# Multivibrator.net
KiCad netlist of a schematic drawn in Altium Designer
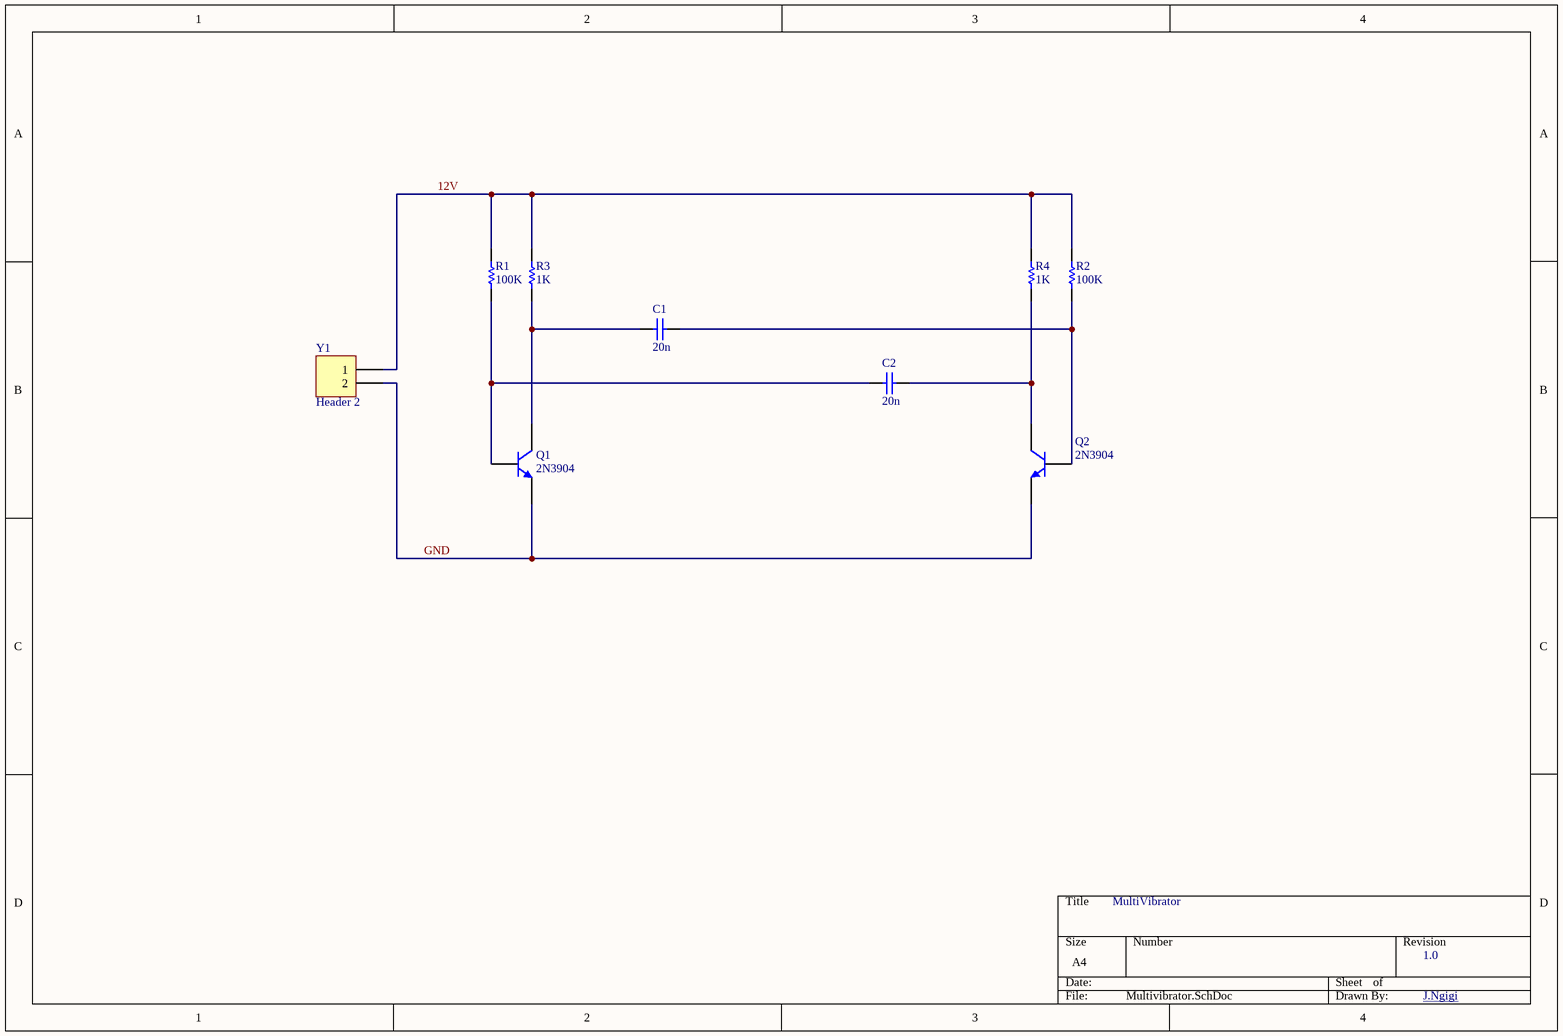
[diagram p0: Multivibrator.SchDoc]

(export (version "E")
  (design (tool "Eeschema 10.0.6"))
  (components
    (comp (ref "C1")
      (value "20n")
      (footprint "RAD-0.3")
      (description "Capacitor")
      (fields (field (name "PUBLISHER") "Altium Limited"))
      (libsource (lib "Miscellaneous Devices") (part "Cap"))
    )
    (comp (ref "C2")
      (value "20n")
      (footprint "RAD-0.3")
      (description "Capacitor")
      (fields (field (name "PUBLISHER") "Altium Limited"))
      (libsource (lib "Miscellaneous Devices") (part "Cap"))
    )
    (comp (ref "Q1")
      (value "2N3904")
      (footprint "TO-92A")
      (description "NPN General Purpose Amplifier")
      (fields (field (name "PUBLISHER") "Altium Limited"))
      (libsource (lib "Miscellaneous Devices") (part "2N3904"))
    )
    (comp (ref "Q2")
      (value "2N3904")
      (footprint "TO-92A")
      (description "NPN General Purpose Amplifier")
      (fields (field (name "PUBLISHER") "Altium Limited"))
      (libsource (lib "Miscellaneous Devices") (part "2N3904"))
    )
    (comp (ref "R1")
      (value "100K")
      (footprint "AXIAL-0.3")
      (description "Resistor")
      (fields (field (name "PUBLISHER") "Altium Limited"))
      (libsource (lib "Miscellaneous Devices") (part "Res1"))
    )
    (comp (ref "R2")
      (value "100K")
      (footprint "AXIAL-0.3")
      (description "Resistor")
      (fields (field (name "PUBLISHER") "Altium Limited"))
      (libsource (lib "Miscellaneous Devices") (part "Res1"))
    )
    (comp (ref "R3")
      (value "1K")
      (footprint "AXIAL-0.3")
      (description "Resistor")
      (fields (field (name "PUBLISHER") "Altium Limited"))
      (libsource (lib "Miscellaneous Devices") (part "Res1"))
    )
    (comp (ref "R4")
      (value "1K")
      (footprint "AXIAL-0.3")
      (description "Resistor")
      (fields (field (name "PUBLISHER") "Altium Limited"))
      (libsource (lib "Miscellaneous Devices") (part "Res1"))
    )
    (comp (ref "Y1")
      (value "Header 2")
      (footprint "HDR1X2")
      (description "Header, 2-Pin")
      (fields (field (name "PUBLISHER") "Altium Limited"))
      (libsource (lib "Miscellaneous Connectors") (part "Header 2"))
    )
  )
  (nets
    (net (code "1") (name "/12V") (class "Default")
      (node (ref "R1") (pin "2") (pinfunction "2_2") (pintype "passive"))
      (node (ref "R2") (pin "2") (pinfunction "2_2") (pintype "passive"))
      (node (ref "R3") (pin "2") (pinfunction "2_2") (pintype "passive"))
      (node (ref "R4") (pin "2") (pinfunction "2_2") (pintype "passive"))
      (node (ref "Y1") (pin "1") (pinfunction "1_1") (pintype "passive"))
    )
    (net (code "2") (name "/GND") (class "Default")
      (node (ref "Q1") (pin "1") (pinfunction "E_1") (pintype "passive"))
      (node (ref "Q2") (pin "1") (pinfunction "E_1") (pintype "passive"))
      (node (ref "Y1") (pin "2") (pinfunction "2_2") (pintype "passive"))
    )
    (net (code "3") (name "Net-(Q1-B)") (class "Default")
      (node (ref "C2") (pin "1") (pinfunction "1_1") (pintype "passive"))
      (node (ref "Q1") (pin "2") (pinfunction "B_2") (pintype "passive"))
      (node (ref "R1") (pin "1") (pinfunction "1_1") (pintype "passive"))
    )
    (net (code "4") (name "Net-(Q1-C)") (class "Default")
      (node (ref "C1") (pin "1") (pinfunction "1_1") (pintype "passive"))
      (node (ref "Q1") (pin "3") (pinfunction "C_3") (pintype "passive"))
      (node (ref "R3") (pin "1") (pinfunction "1_1") (pintype "passive"))
    )
    (net (code "5") (name "Net-(Q2-B)") (class "Default")
      (node (ref "C1") (pin "2") (pinfunction "2_2") (pintype "passive"))
      (node (ref "Q2") (pin "2") (pinfunction "B_2") (pintype "passive"))
      (node (ref "R2") (pin "1") (pinfunction "1_1") (pintype "passive"))
    )
    (net (code "6") (name "Net-(Q2-C)") (class "Default")
      (node (ref "C2") (pin "2") (pinfunction "2_2") (pintype "passive"))
      (node (ref "Q2") (pin "3") (pinfunction "C_3") (pintype "passive"))
      (node (ref "R4") (pin "1") (pinfunction "1_1") (pintype "passive"))
    )
  )
)
